# RGB-strip-connector-v2.net
KiCad netlist of a schematic drawn in EAGLE
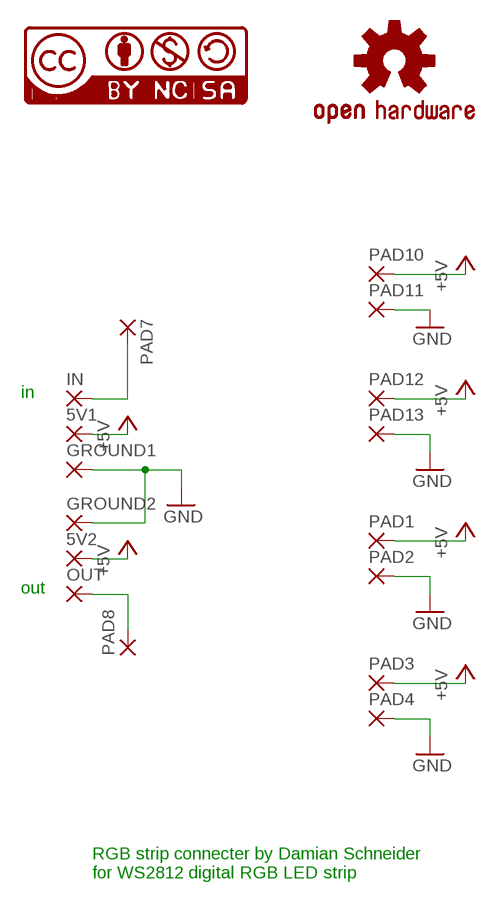
[diagram p0: schematic, sheet 1]

(export (version "E")
  (design (tool "Eeschema 10.0.6"))
  (components
    (comp (ref "5V1")
      (value "SMD2")
      (footprint "eagle-import:SMD1,27-2,54")
      (libsource (lib "eagle-import") (part "SMD2"))
    )
    (comp (ref "5V2")
      (value "SMD2")
      (footprint "eagle-import:SMD1,27-2,54")
      (libsource (lib "eagle-import") (part "SMD2"))
    )
    (comp (ref "GROUND1")
      (value "SMD2")
      (footprint "eagle-import:SMD1,27-2,54")
      (libsource (lib "eagle-import") (part "SMD2"))
    )
    (comp (ref "GROUND2")
      (value "SMD2")
      (footprint "eagle-import:SMD1,27-2,54")
      (libsource (lib "eagle-import") (part "SMD2"))
    )
    (comp (ref "IN")
      (value "SMD2")
      (footprint "eagle-import:SMD1,27-2,54")
      (libsource (lib "eagle-import") (part "SMD2"))
    )
    (comp (ref "LOGO1")
      (value "OSHW-LOGOL")
      (footprint "eagle-import:OSHW-LOGO-L")
      (libsource (lib "eagle-import") (part "OSHW-LOGOL"))
    )
    (comp (ref "OUT")
      (value "SMD2")
      (footprint "eagle-import:SMD1,27-2,54")
      (libsource (lib "eagle-import") (part "SMD2"))
    )
    (comp (ref "PAD1")
      (value "SMD5")
      (footprint "eagle-import:SMD2,54-5,08")
      (libsource (lib "eagle-import") (part "SMD5"))
    )
    (comp (ref "PAD2")
      (value "SMD5")
      (footprint "eagle-import:SMD2,54-5,08")
      (libsource (lib "eagle-import") (part "SMD5"))
    )
    (comp (ref "PAD3")
      (value "SMD5")
      (footprint "eagle-import:SMD2,54-5,08")
      (libsource (lib "eagle-import") (part "SMD5"))
    )
    (comp (ref "PAD4")
      (value "SMD5")
      (footprint "eagle-import:SMD2,54-5,08")
      (libsource (lib "eagle-import") (part "SMD5"))
    )
    (comp (ref "PAD7")
      (value "SMD2")
      (footprint "eagle-import:SMD1,27-2,54")
      (libsource (lib "eagle-import") (part "SMD2"))
    )
    (comp (ref "PAD8")
      (value "SMD2")
      (footprint "eagle-import:SMD1,27-2,54")
      (libsource (lib "eagle-import") (part "SMD2"))
    )
    (comp (ref "PAD10")
      (value "SMD5")
      (footprint "eagle-import:SMD2,54-5,08")
      (libsource (lib "eagle-import") (part "SMD5"))
    )
    (comp (ref "PAD11")
      (value "SMD5")
      (footprint "eagle-import:SMD2,54-5,08")
      (libsource (lib "eagle-import") (part "SMD5"))
    )
    (comp (ref "PAD12")
      (value "SMD5")
      (footprint "eagle-import:SMD2,54-5,08")
      (libsource (lib "eagle-import") (part "SMD5"))
    )
    (comp (ref "PAD13")
      (value "SMD5")
      (footprint "eagle-import:SMD2,54-5,08")
      (libsource (lib "eagle-import") (part "SMD5"))
    )
    (comp (ref "U$1")
      (value "CC-NC-BCNIX")
      (footprint "eagle-import:CC-NC-B_NIX")
      (libsource (lib "eagle-import") (part "CC-NC-BCNIX"))
    )
  )
  (nets
    (net (code "1") (name "+5V") (class "Default")
      (node (ref "5V1") (pin "1") (pinfunction "P_1") (pintype "passive"))
      (node (ref "5V2") (pin "1") (pinfunction "P_1") (pintype "passive"))
      (node (ref "PAD1") (pin "1") (pinfunction "P_1") (pintype "passive"))
      (node (ref "PAD10") (pin "1") (pinfunction "P_1") (pintype "passive"))
      (node (ref "PAD12") (pin "1") (pinfunction "P_1") (pintype "passive"))
      (node (ref "PAD3") (pin "1") (pinfunction "P_1") (pintype "passive"))
    )
    (net (code "2") (name "GND") (class "Default")
      (node (ref "GROUND1") (pin "1") (pinfunction "P_1") (pintype "passive"))
      (node (ref "GROUND2") (pin "1") (pinfunction "P_1") (pintype "passive"))
      (node (ref "PAD11") (pin "1") (pinfunction "P_1") (pintype "passive"))
      (node (ref "PAD13") (pin "1") (pinfunction "P_1") (pintype "passive"))
      (node (ref "PAD2") (pin "1") (pinfunction "P_1") (pintype "passive"))
      (node (ref "PAD4") (pin "1") (pinfunction "P_1") (pintype "passive"))
    )
    (net (code "3") (name "Net-(IN-P)") (class "Default")
      (node (ref "IN") (pin "1") (pinfunction "P_1") (pintype "passive"))
      (node (ref "PAD7") (pin "1") (pinfunction "P_1") (pintype "passive"))
    )
    (net (code "4") (name "Net-(OUT-P)") (class "Default")
      (node (ref "OUT") (pin "1") (pinfunction "P_1") (pintype "passive"))
      (node (ref "PAD8") (pin "1") (pinfunction "P_1") (pintype "passive"))
    )
  )
)
